# rfid_module_v3.net
KiCad netlist of a schematic drawn in EAGLE
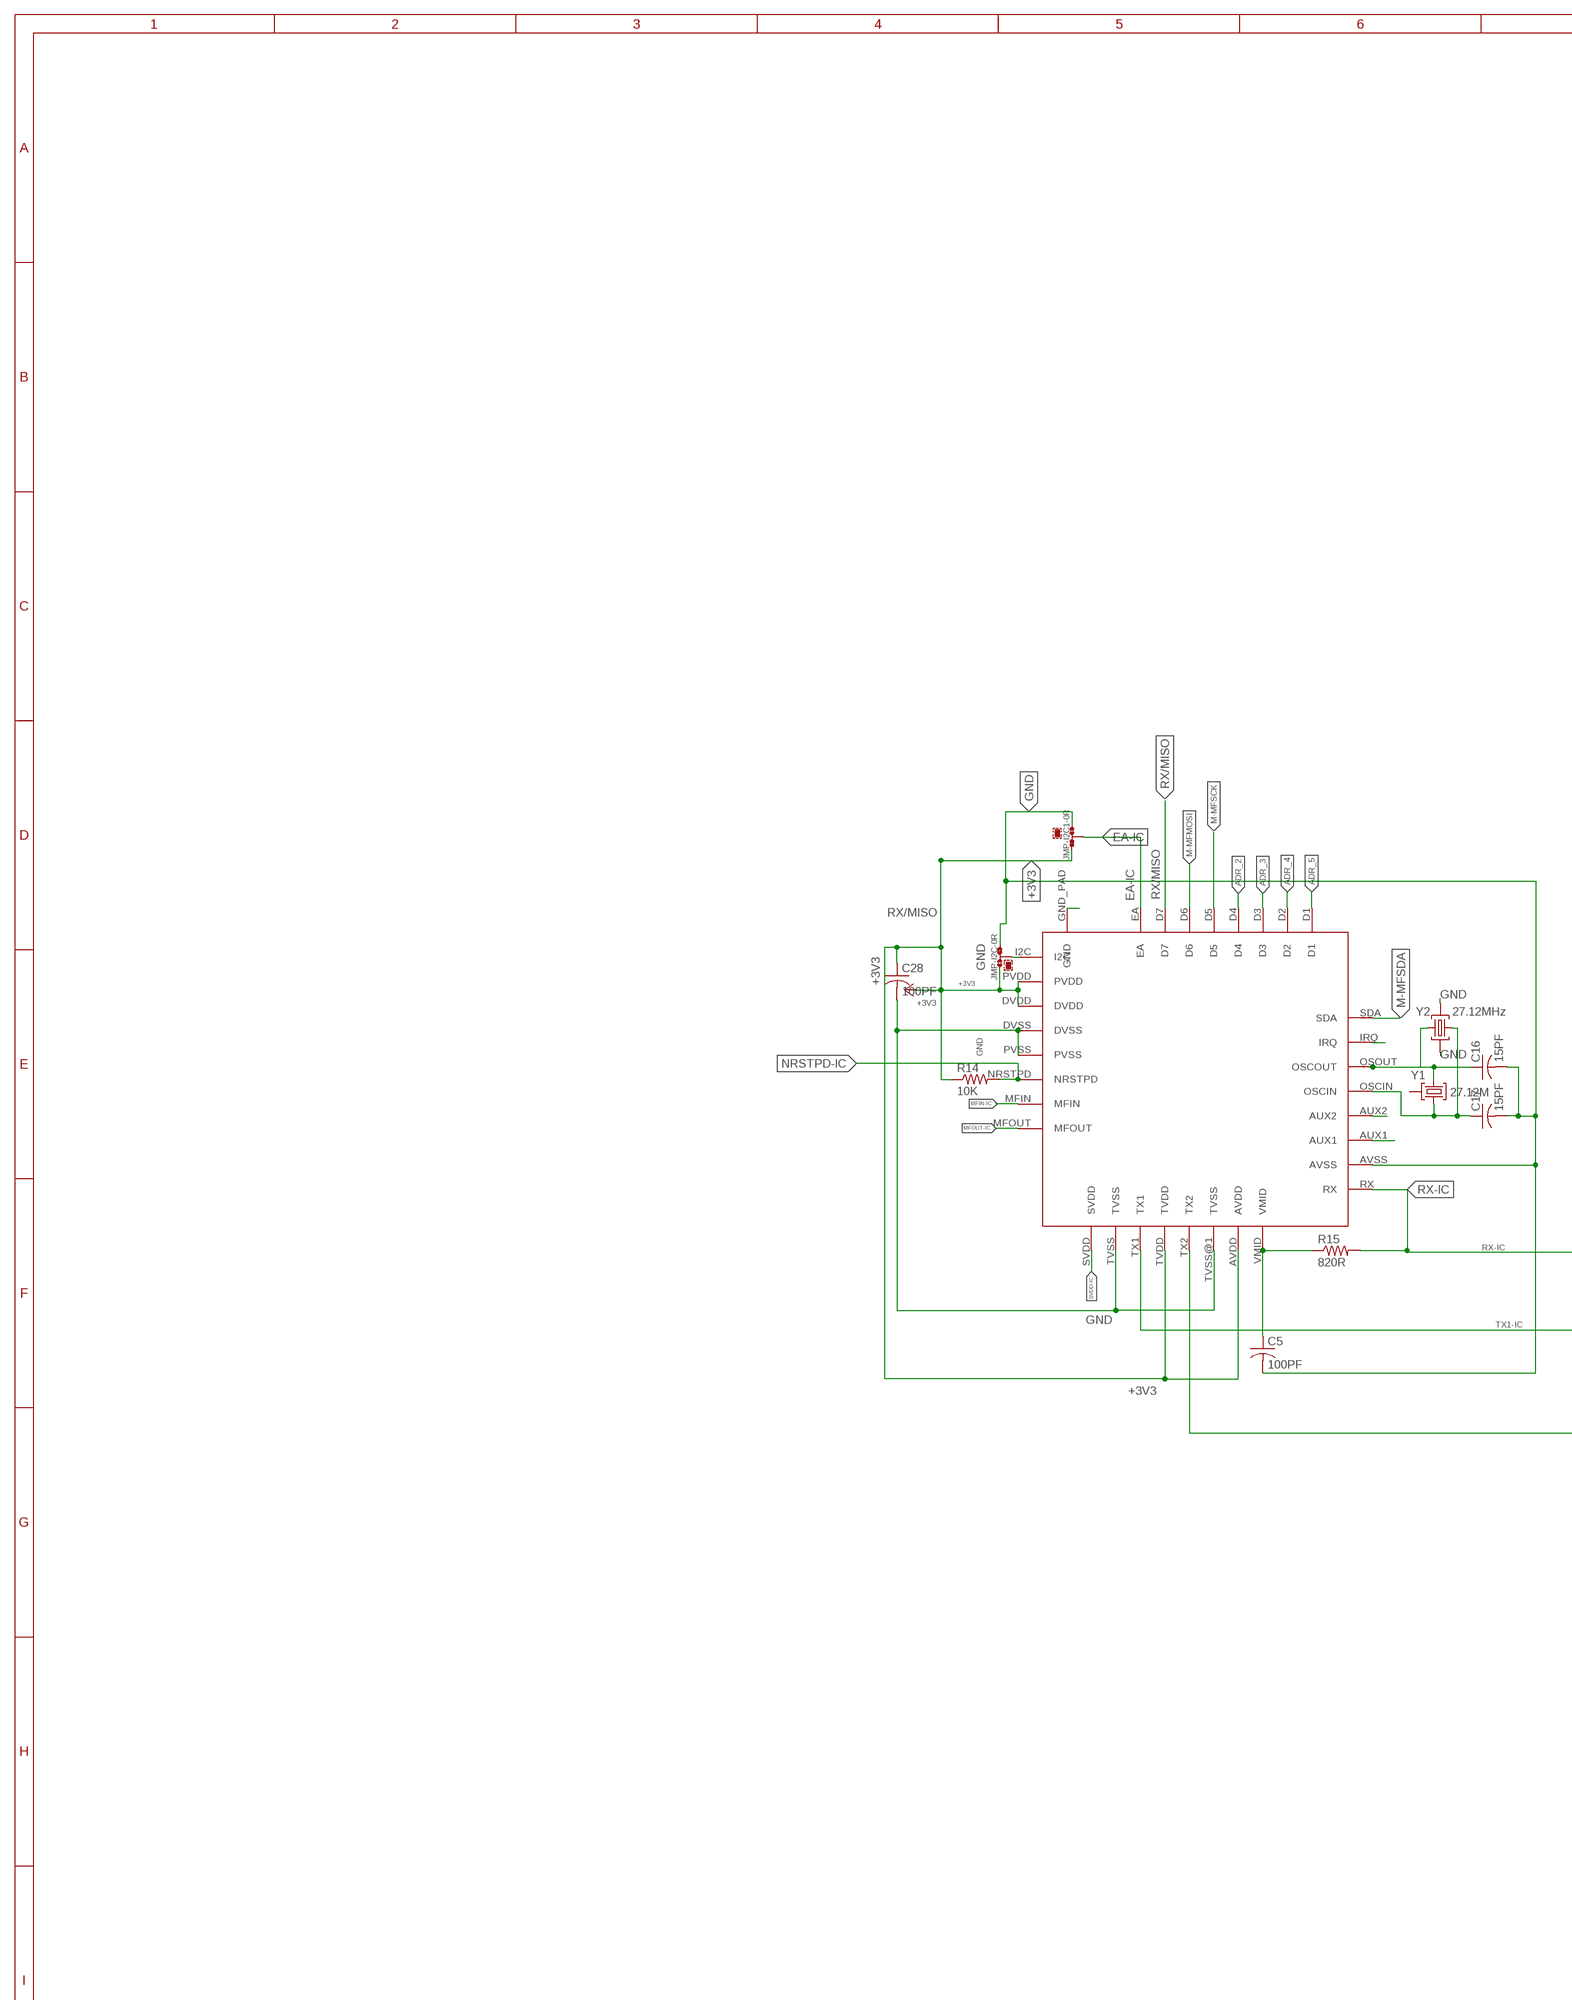
[diagram p0: schematic, sheet 1, part 1 of 2]
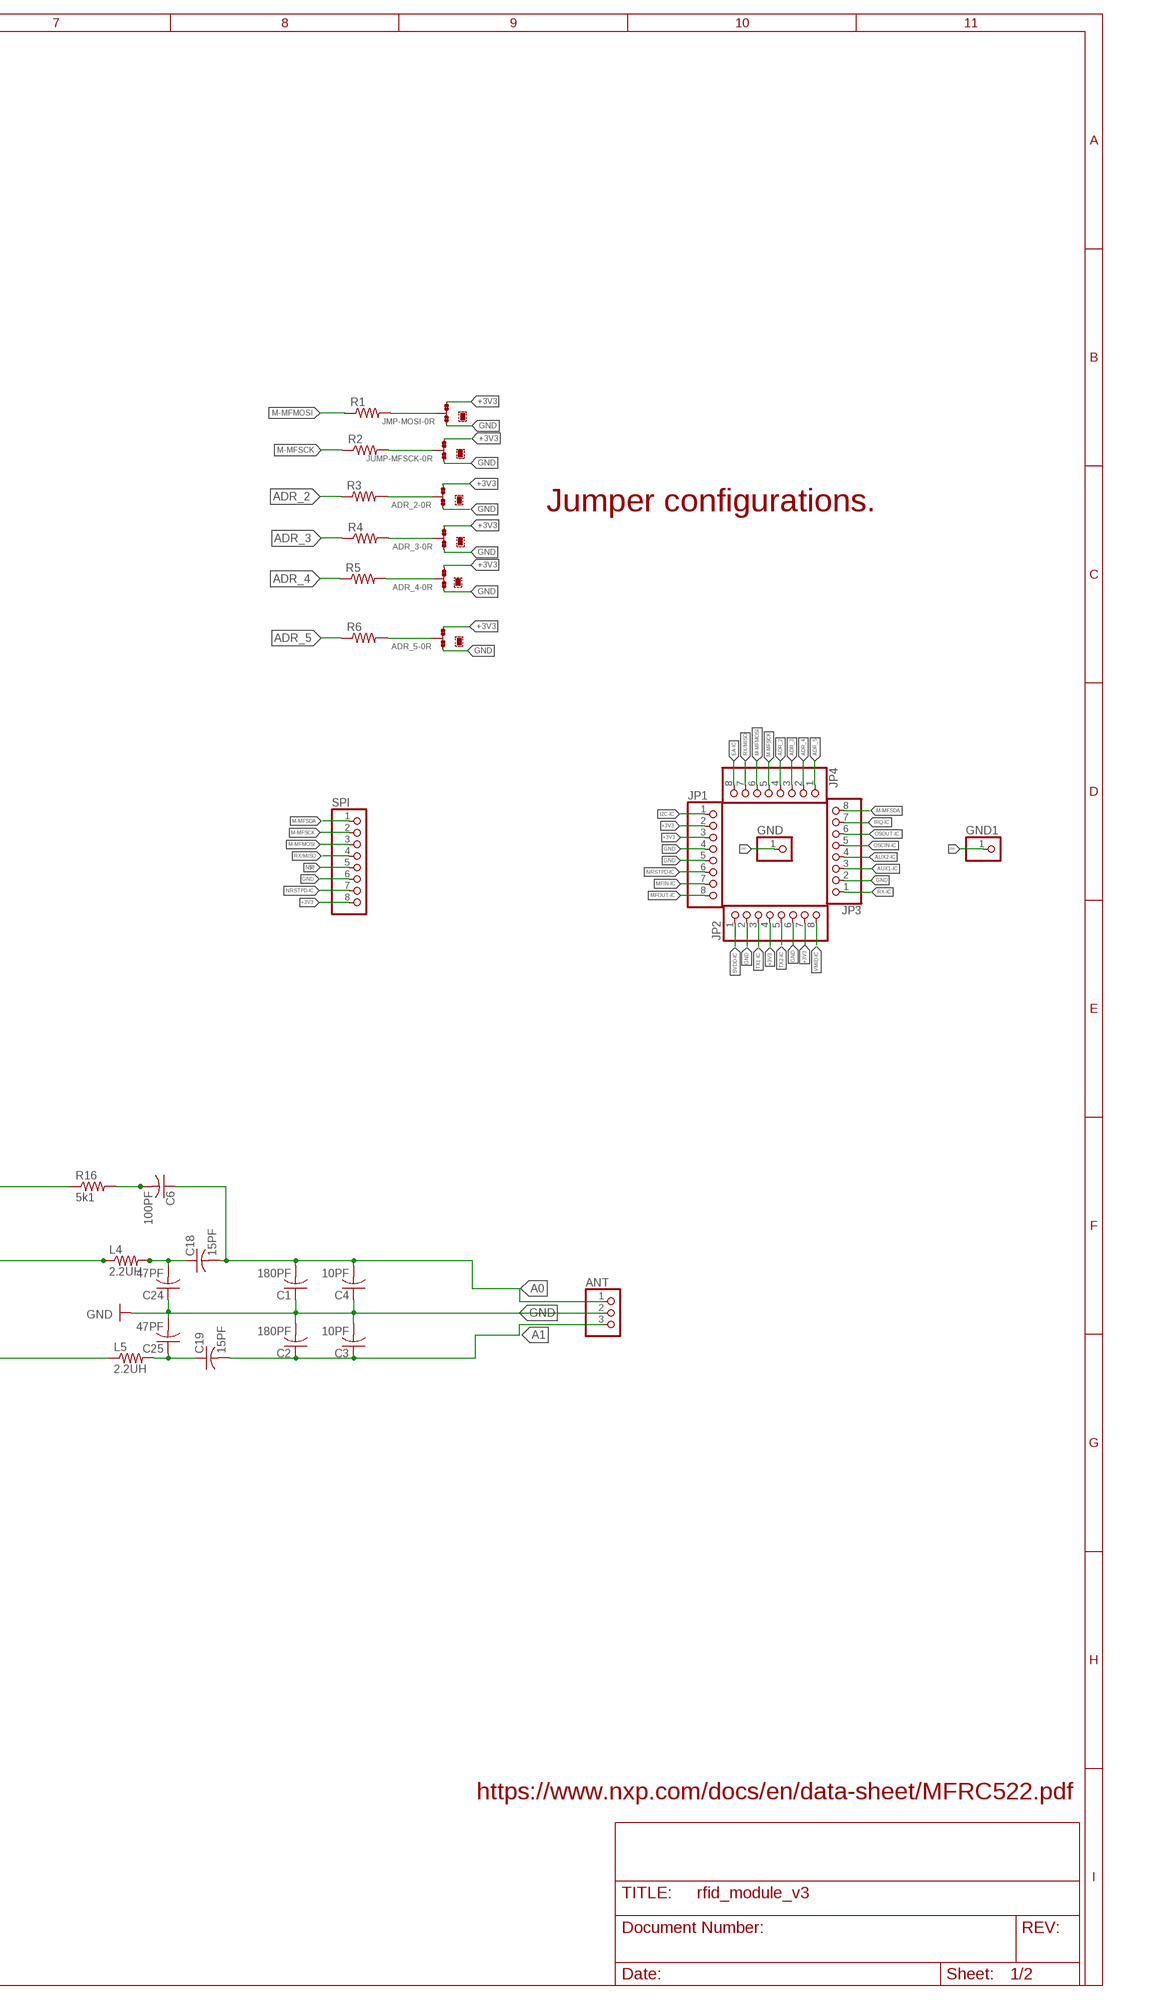
[diagram p1: schematic, sheet 1, part 2 of 2]
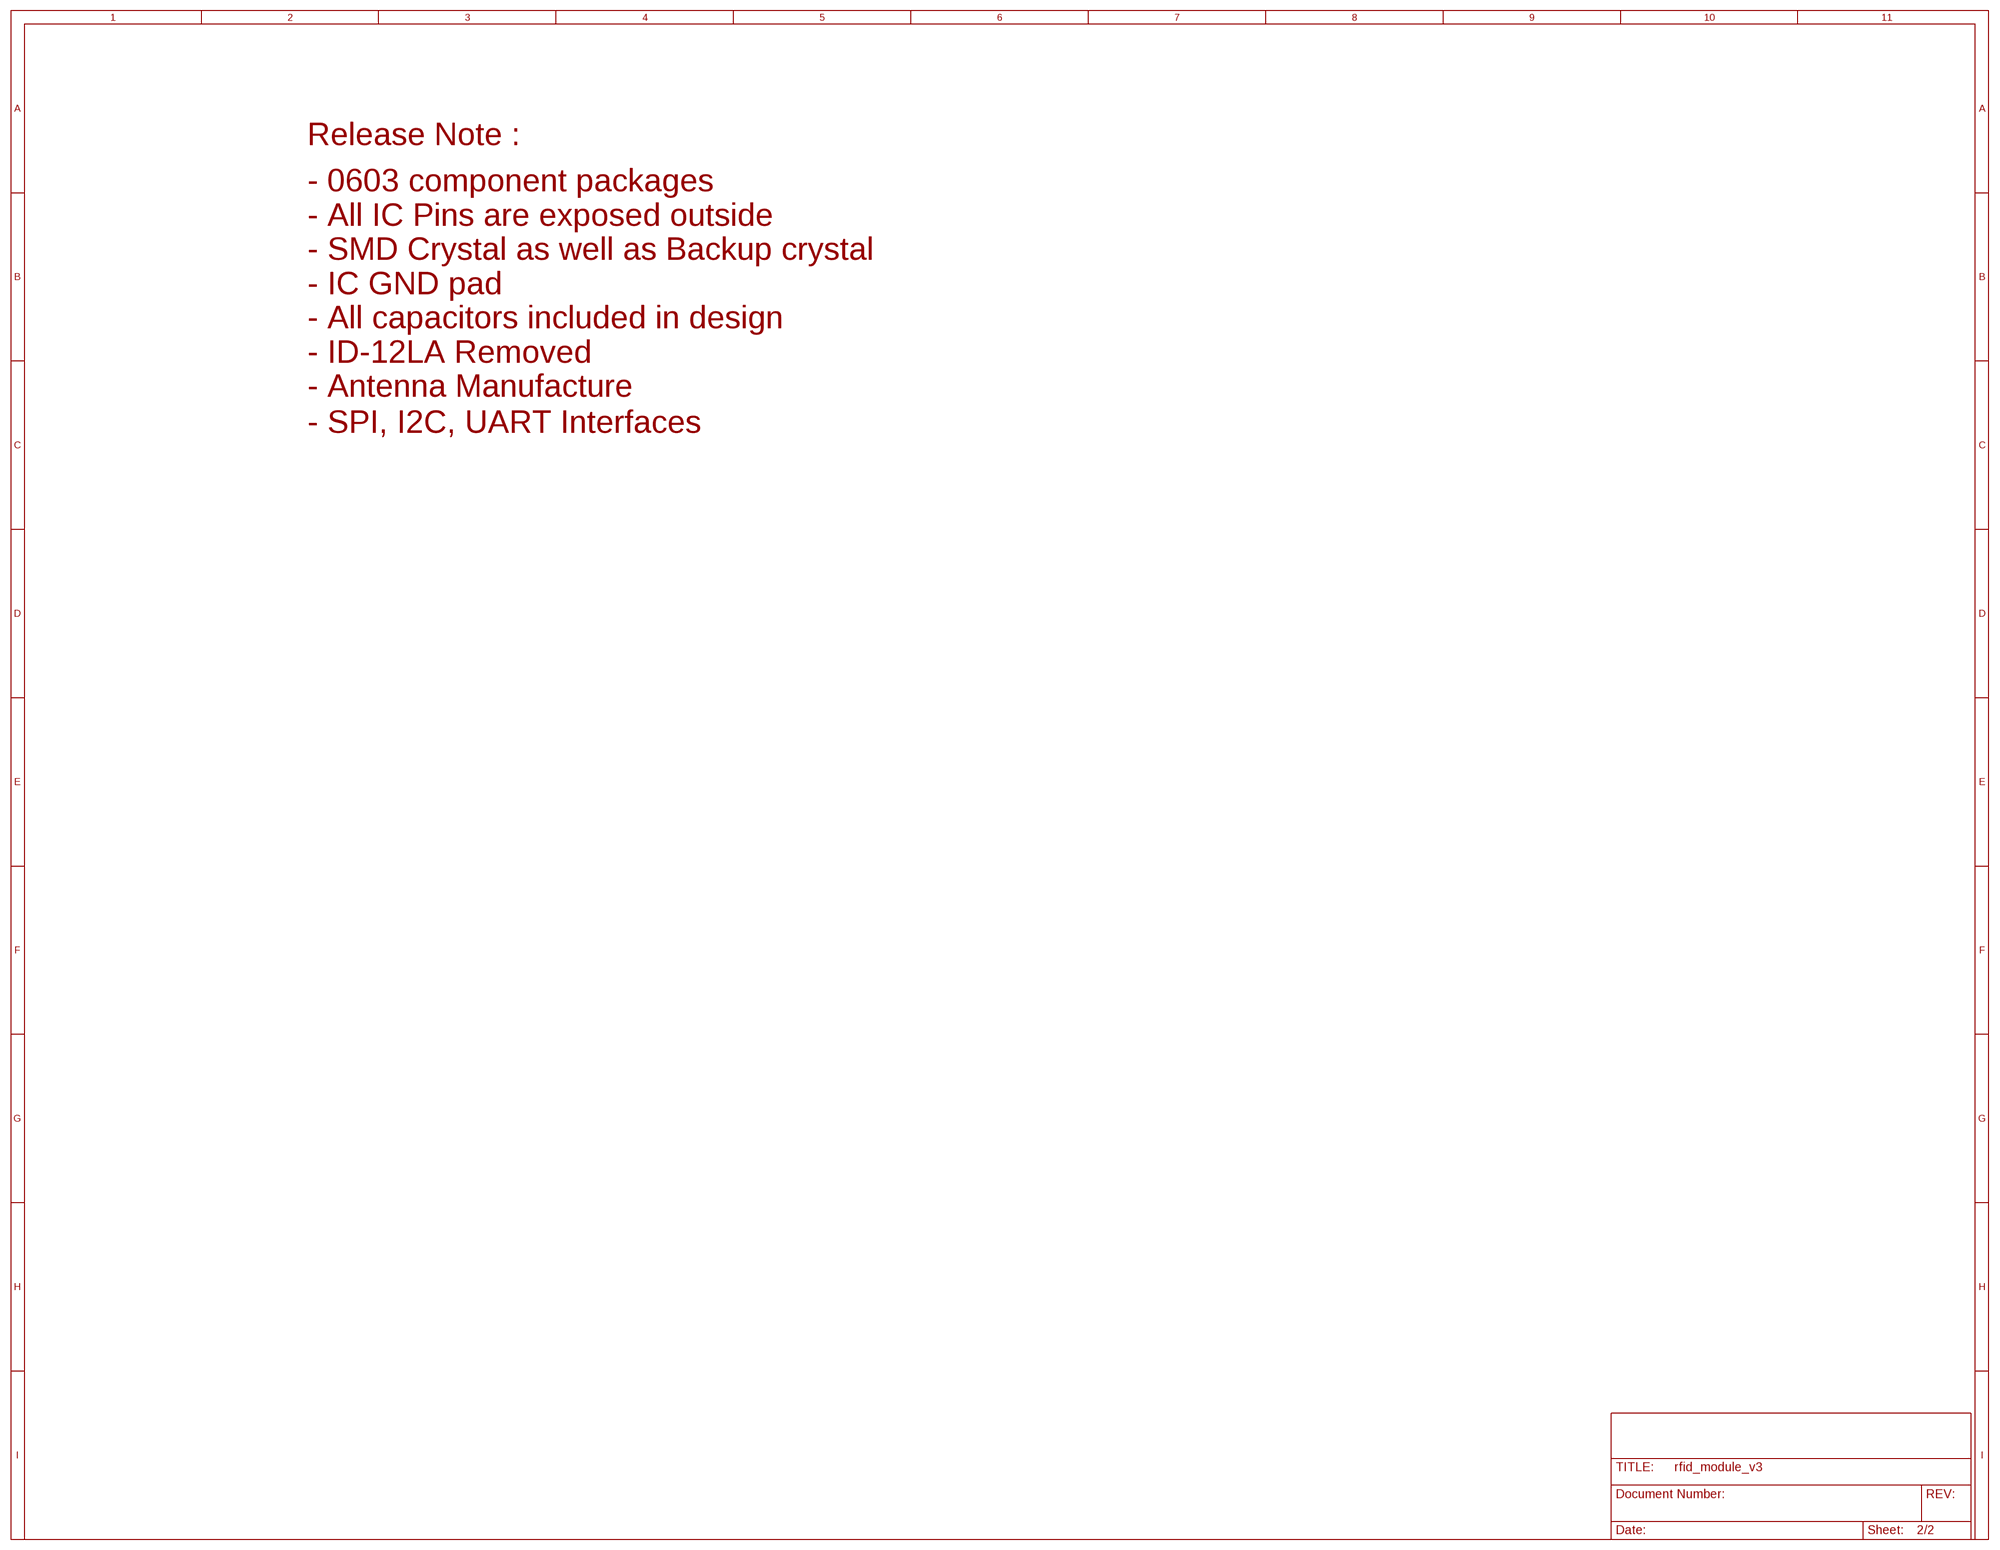
[diagram p2: schematic, sheet 2]

(export (version "E")
  (design (tool "Eeschema 10.0.6"))
  (components
    (comp (ref "ADR_2")
      (value "0R-JUMPA")
      (footprint "eagle-import:A0R-JMP")
      (libsource (lib "eagle-import") (part "0R-JUMPA"))
    )
    (comp (ref "ADR_3")
      (value "0R-JUMPA")
      (footprint "eagle-import:A0R-JMP")
      (libsource (lib "eagle-import") (part "0R-JUMPA"))
    )
    (comp (ref "ADR_4")
      (value "0R-JUMPA")
      (footprint "eagle-import:A0R-JMP")
      (libsource (lib "eagle-import") (part "0R-JUMPA"))
    )
    (comp (ref "ADR_5")
      (value "0R-JUMPA")
      (footprint "eagle-import:A0R-JMP")
      (libsource (lib "eagle-import") (part "0R-JUMPA"))
    )
    (comp (ref "ANT")
      (value "PINHD-1X3")
      (footprint "eagle-import:1X03")
      (libsource (lib "eagle-import") (part "PINHD-1X3"))
    )
    (comp (ref "C1")
      (value "180PF")
      (footprint "eagle-import:C0603")
      (libsource (lib "eagle-import") (part "C-USC0603"))
    )
    (comp (ref "C2")
      (value "180PF")
      (footprint "eagle-import:C0603")
      (libsource (lib "eagle-import") (part "C-USC0603"))
    )
    (comp (ref "C3")
      (value "10PF")
      (footprint "eagle-import:C0603")
      (libsource (lib "eagle-import") (part "C-USC0603"))
    )
    (comp (ref "C4")
      (value "10PF")
      (footprint "eagle-import:C0603")
      (libsource (lib "eagle-import") (part "C-USC0603"))
    )
    (comp (ref "C5")
      (value "100PF")
      (footprint "eagle-import:C0603")
      (libsource (lib "eagle-import") (part "C-USC0603"))
    )
    (comp (ref "C6")
      (value "100PF")
      (footprint "eagle-import:C0603")
      (libsource (lib "eagle-import") (part "C-USC0603"))
    )
    (comp (ref "C16")
      (value "15PF")
      (footprint "eagle-import:C0603")
      (libsource (lib "eagle-import") (part "C-USC0603"))
    )
    (comp (ref "C17")
      (value "15PF")
      (footprint "eagle-import:C0603")
      (libsource (lib "eagle-import") (part "C-USC0603"))
    )
    (comp (ref "C18")
      (value "15PF")
      (footprint "eagle-import:C0603")
      (libsource (lib "eagle-import") (part "C-USC0603"))
    )
    (comp (ref "C19")
      (value "15PF")
      (footprint "eagle-import:C0603")
      (libsource (lib "eagle-import") (part "C-USC0603"))
    )
    (comp (ref "C24")
      (value "47PF")
      (footprint "eagle-import:C0603")
      (libsource (lib "eagle-import") (part "C-USC0603"))
    )
    (comp (ref "C25")
      (value "47PF")
      (footprint "eagle-import:C0603")
      (libsource (lib "eagle-import") (part "C-USC0603"))
    )
    (comp (ref "C28")
      (value "100PF")
      (footprint "eagle-import:C0603")
      (libsource (lib "eagle-import") (part "C-USC0603"))
    )
    (comp (ref "GND")
      (value "PINHD-1X1")
      (footprint "eagle-import:1X01")
      (libsource (lib "eagle-import") (part "PINHD-1X1"))
    )
    (comp (ref "GND1")
      (value "PINHD-1X1")
      (footprint "eagle-import:1X01")
      (libsource (lib "eagle-import") (part "PINHD-1X1"))
    )
    (comp (ref "JMP-I2C")
      (value "0R-JUMPA")
      (footprint "eagle-import:A0R-JMP")
      (libsource (lib "eagle-import") (part "0R-JUMPA"))
    )
    (comp (ref "JMP-I2C1")
      (value "JMP-EA")
      (footprint "eagle-import:A0R-JMP")
      (libsource (lib "eagle-import") (part "0R-JUMPA"))
    )
    (comp (ref "JMP-MOSI")
      (value "0R-JUMPA")
      (footprint "eagle-import:A0R-JMP")
      (libsource (lib "eagle-import") (part "0R-JUMPA"))
    )
    (comp (ref "JP1")
      (value "PINHD-1X8")
      (footprint "eagle-import:1X08")
      (libsource (lib "eagle-import") (part "PINHD-1X8"))
    )
    (comp (ref "JP2")
      (value "PINHD-1X8")
      (footprint "eagle-import:1X08")
      (libsource (lib "eagle-import") (part "PINHD-1X8"))
    )
    (comp (ref "JP3")
      (value "PINHD-1X8")
      (footprint "eagle-import:1X08")
      (libsource (lib "eagle-import") (part "PINHD-1X8"))
    )
    (comp (ref "JP4")
      (value "PINHD-1X8")
      (footprint "eagle-import:1X08")
      (libsource (lib "eagle-import") (part "PINHD-1X8"))
    )
    (comp (ref "JUMP-MFSCK")
      (value "0R-JUMPA")
      (footprint "eagle-import:A0R-JMP")
      (libsource (lib "eagle-import") (part "0R-JUMPA"))
    )
    (comp (ref "L4")
      (value "2.2UH")
      (footprint "eagle-import:R0603")
      (libsource (lib "eagle-import") (part "R-US_R0603"))
    )
    (comp (ref "L5")
      (value "2.2UH")
      (footprint "eagle-import:R0603")
      (libsource (lib "eagle-import") (part "R-US_R0603"))
    )
    (comp (ref "R1")
      (value "R-US_R0603")
      (footprint "eagle-import:R0603")
      (libsource (lib "eagle-import") (part "R-US_R0603"))
    )
    (comp (ref "R2")
      (value "R-US_R0603")
      (footprint "eagle-import:R0603")
      (libsource (lib "eagle-import") (part "R-US_R0603"))
    )
    (comp (ref "R3")
      (value "R-US_R0603")
      (footprint "eagle-import:R0603")
      (libsource (lib "eagle-import") (part "R-US_R0603"))
    )
    (comp (ref "R4")
      (value "R-US_R0603")
      (footprint "eagle-import:R0603")
      (libsource (lib "eagle-import") (part "R-US_R0603"))
    )
    (comp (ref "R5")
      (value "R-US_R0603")
      (footprint "eagle-import:R0603")
      (libsource (lib "eagle-import") (part "R-US_R0603"))
    )
    (comp (ref "R6")
      (value "R-US_R0603")
      (footprint "eagle-import:R0603")
      (libsource (lib "eagle-import") (part "R-US_R0603"))
    )
    (comp (ref "R14")
      (value "10K")
      (footprint "eagle-import:R0603")
      (libsource (lib "eagle-import") (part "R-US_R0603"))
    )
    (comp (ref "R15")
      (value "820R")
      (footprint "eagle-import:R0603")
      (libsource (lib "eagle-import") (part "R-US_R0603"))
    )
    (comp (ref "R16")
      (value "5k1")
      (footprint "eagle-import:R0603")
      (libsource (lib "eagle-import") (part "R-US_R0603"))
    )
    (comp (ref "SPI")
      (value "PINHD-1X8")
      (footprint "eagle-import:1X08")
      (libsource (lib "eagle-import") (part "PINHD-1X8"))
    )
    (comp (ref "U$1")
      (value "MFRC522")
      (footprint "eagle-import:MFRC522")
      (libsource (lib "eagle-import") (part "MFRC522"))
    )
    (comp (ref "Y1")
      (value "27.12M")
      (footprint "eagle-import:RAD3LEAD")
      (libsource (lib "eagle-import") (part "CRYSTAL"))
    )
    (comp (ref "Y2")
      (value "27.12MHz")
      (footprint "eagle-import:CRYSTAL-3.2-2.5")
      (libsource (lib "eagle-import") (part "CRYSTAL-3.2-2.5"))
    )
  )
  (nets
    (net (code "1") (name "+3V3") (class "Default")
      (node (ref "ADR_2") (pin "3") (pinfunction "3_3") (pintype "passive"))
      (node (ref "ADR_3") (pin "3") (pinfunction "3_3") (pintype "passive"))
      (node (ref "ADR_4") (pin "3") (pinfunction "3_3") (pintype "passive"))
      (node (ref "ADR_5") (pin "3") (pinfunction "3_3") (pintype "passive"))
      (node (ref "C28") (pin "1") (pinfunction "1_1") (pintype "passive"))
      (node (ref "JMP-I2C") (pin "3") (pinfunction "3_3") (pintype "passive"))
      (node (ref "JMP-I2C1") (pin "3") (pinfunction "3_3") (pintype "passive"))
      (node (ref "JMP-MOSI") (pin "3") (pinfunction "3_3") (pintype "passive"))
      (node (ref "JP1") (pin "2") (pinfunction "2_2") (pintype "passive"))
      (node (ref "JP1") (pin "3") (pinfunction "3_3") (pintype "passive"))
      (node (ref "JP2") (pin "4") (pinfunction "4_4") (pintype "passive"))
      (node (ref "JP2") (pin "7") (pinfunction "7_7") (pintype "passive"))
      (node (ref "JUMP-MFSCK") (pin "3") (pinfunction "3_3") (pintype "passive"))
      (node (ref "R14") (pin "1") (pinfunction "1_1") (pintype "passive"))
      (node (ref "SPI") (pin "8") (pinfunction "8_8") (pintype "passive"))
      (node (ref "U$1") (pin "AVDD") (pinfunction "AVDD_AVDD") (pintype "bidirectional"))
      (node (ref "U$1") (pin "DVDD") (pinfunction "DVDD_DVDD") (pintype "bidirectional"))
      (node (ref "U$1") (pin "PVDD") (pinfunction "PVDD_PVDD") (pintype "bidirectional"))
      (node (ref "U$1") (pin "TVDD") (pinfunction "TVDD_TVDD") (pintype "bidirectional"))
    )
    (net (code "2") (name "A0") (class "Default")
      (node (ref "ANT") (pin "1") (pinfunction "1_1") (pintype "passive"))
      (node (ref "C1") (pin "2") (pinfunction "2_2") (pintype "passive"))
      (node (ref "C18") (pin "2") (pinfunction "2_2") (pintype "passive"))
      (node (ref "C4") (pin "2") (pinfunction "2_2") (pintype "passive"))
      (node (ref "C6") (pin "1") (pinfunction "1_1") (pintype "passive"))
    )
    (net (code "3") (name "A1") (class "Default")
      (node (ref "ANT") (pin "3") (pinfunction "3_3") (pintype "passive"))
      (node (ref "C19") (pin "2") (pinfunction "2_2") (pintype "passive"))
      (node (ref "C2") (pin "1") (pinfunction "1_1") (pintype "passive"))
      (node (ref "C3") (pin "1") (pinfunction "1_1") (pintype "passive"))
    )
    (net (code "4") (name "ADR_2") (class "Default")
      (node (ref "JP4") (pin "4") (pinfunction "4_4") (pintype "passive"))
      (node (ref "R3") (pin "1") (pinfunction "1_1") (pintype "passive"))
      (node (ref "U$1") (pin "D4") (pinfunction "D4_D4") (pintype "bidirectional"))
    )
    (net (code "5") (name "ADR_3") (class "Default")
      (node (ref "JP4") (pin "3") (pinfunction "3_3") (pintype "passive"))
      (node (ref "R4") (pin "1") (pinfunction "1_1") (pintype "passive"))
      (node (ref "U$1") (pin "D3") (pinfunction "D3_D3") (pintype "bidirectional"))
    )
    (net (code "6") (name "ADR_4") (class "Default")
      (node (ref "JP4") (pin "2") (pinfunction "2_2") (pintype "passive"))
      (node (ref "R5") (pin "1") (pinfunction "1_1") (pintype "passive"))
      (node (ref "U$1") (pin "D2") (pinfunction "D2_D2") (pintype "bidirectional"))
    )
    (net (code "7") (name "ADR_5") (class "Default")
      (node (ref "JP4") (pin "1") (pinfunction "1_1") (pintype "passive"))
      (node (ref "R6") (pin "1") (pinfunction "1_1") (pintype "passive"))
      (node (ref "U$1") (pin "D1") (pinfunction "D1_D1") (pintype "bidirectional"))
    )
    (net (code "8") (name "AUX1-IC") (class "Default")
      (node (ref "JP3") (pin "3") (pinfunction "3_3") (pintype "passive"))
      (node (ref "U$1") (pin "AUX1") (pinfunction "AUX1_AUX1") (pintype "bidirectional"))
    )
    (net (code "9") (name "AUX2-IC") (class "Default")
      (node (ref "JP3") (pin "4") (pinfunction "4_4") (pintype "passive"))
      (node (ref "U$1") (pin "AUX2") (pinfunction "AUX2_AUX2") (pintype "bidirectional"))
    )
    (net (code "10") (name "EA-IC") (class "Default")
      (node (ref "JMP-I2C1") (pin "2") (pinfunction "2_2") (pintype "passive"))
      (node (ref "JP4") (pin "8") (pinfunction "8_8") (pintype "passive"))
      (node (ref "U$1") (pin "EA") (pinfunction "EA_EA") (pintype "bidirectional"))
    )
    (net (code "11") (name "GND") (class "Default")
      (node (ref "ADR_2") (pin "1") (pinfunction "1_1") (pintype "passive"))
      (node (ref "ADR_3") (pin "1") (pinfunction "1_1") (pintype "passive"))
      (node (ref "ADR_4") (pin "1") (pinfunction "1_1") (pintype "passive"))
      (node (ref "ADR_5") (pin "1") (pinfunction "1_1") (pintype "passive"))
      (node (ref "ANT") (pin "2") (pinfunction "2_2") (pintype "passive"))
      (node (ref "C1") (pin "1") (pinfunction "1_1") (pintype "passive"))
      (node (ref "C16") (pin "2") (pinfunction "2_2") (pintype "passive"))
      (node (ref "C17") (pin "2") (pinfunction "2_2") (pintype "passive"))
      (node (ref "C2") (pin "2") (pinfunction "2_2") (pintype "passive"))
      (node (ref "C24") (pin "1") (pinfunction "1_1") (pintype "passive"))
      (node (ref "C25") (pin "2") (pinfunction "2_2") (pintype "passive"))
      (node (ref "C28") (pin "2") (pinfunction "2_2") (pintype "passive"))
      (node (ref "C3") (pin "2") (pinfunction "2_2") (pintype "passive"))
      (node (ref "C4") (pin "1") (pinfunction "1_1") (pintype "passive"))
      (node (ref "C5") (pin "2") (pinfunction "2_2") (pintype "passive"))
      (node (ref "GND") (pin "1") (pinfunction "1_1") (pintype "passive"))
      (node (ref "GND1") (pin "1") (pinfunction "1_1") (pintype "passive"))
      (node (ref "JMP-I2C") (pin "1") (pinfunction "1_1") (pintype "passive"))
      (node (ref "JMP-I2C1") (pin "1") (pinfunction "1_1") (pintype "passive"))
      (node (ref "JMP-MOSI") (pin "1") (pinfunction "1_1") (pintype "passive"))
      (node (ref "JP1") (pin "4") (pinfunction "4_4") (pintype "passive"))
      (node (ref "JP1") (pin "5") (pinfunction "5_5") (pintype "passive"))
      (node (ref "JP2") (pin "2") (pinfunction "2_2") (pintype "passive"))
      (node (ref "JP2") (pin "6") (pinfunction "6_6") (pintype "passive"))
      (node (ref "JP3") (pin "2") (pinfunction "2_2") (pintype "passive"))
      (node (ref "JUMP-MFSCK") (pin "1") (pinfunction "1_1") (pintype "passive"))
      (node (ref "SPI") (pin "6") (pinfunction "6_6") (pintype "passive"))
      (node (ref "U$1") (pin "AVSS") (pinfunction "AVSS_AVSS") (pintype "bidirectional"))
      (node (ref "U$1") (pin "DVSS") (pinfunction "DVSS_DVSS") (pintype "bidirectional"))
      (node (ref "U$1") (pin "GND_PAD") (pinfunction "GND_GND_PAD") (pintype "bidirectional"))
      (node (ref "U$1") (pin "PVSS") (pinfunction "PVSS_PVSS") (pintype "bidirectional"))
      (node (ref "U$1") (pin "TVSS") (pinfunction "TVSS_TVSS") (pintype "bidirectional"))
      (node (ref "U$1") (pin "TVSS@1") (pinfunction "TVSS_TVSS@1") (pintype "bidirectional"))
      (node (ref "Y2") (pin "2") (pinfunction "GND_2") (pintype "passive"))
      (node (ref "Y2") (pin "4") (pinfunction "GND_4") (pintype "passive"))
    )
    (net (code "12") (name "I2C-IC") (class "Default")
      (node (ref "JMP-I2C") (pin "2") (pinfunction "2_2") (pintype "passive"))
      (node (ref "JP1") (pin "1") (pinfunction "1_1") (pintype "passive"))
      (node (ref "U$1") (pin "I2C") (pinfunction "I2C_I2C") (pintype "bidirectional"))
    )
    (net (code "13") (name "IRQ-IC") (class "Default")
      (node (ref "JP3") (pin "7") (pinfunction "7_7") (pintype "passive"))
      (node (ref "U$1") (pin "IRQ") (pinfunction "IRQ_IRQ") (pintype "bidirectional"))
    )
    (net (code "14") (name "M-MFMOSI") (class "Default")
      (node (ref "JP4") (pin "6") (pinfunction "6_6") (pintype "passive"))
      (node (ref "R1") (pin "1") (pinfunction "1_1") (pintype "passive"))
      (node (ref "SPI") (pin "3") (pinfunction "3_3") (pintype "passive"))
      (node (ref "U$1") (pin "D6") (pinfunction "D6_D6") (pintype "bidirectional"))
    )
    (net (code "15") (name "M-MFSCK") (class "Default")
      (node (ref "JP4") (pin "5") (pinfunction "5_5") (pintype "passive"))
      (node (ref "R2") (pin "1") (pinfunction "1_1") (pintype "passive"))
      (node (ref "SPI") (pin "2") (pinfunction "2_2") (pintype "passive"))
      (node (ref "U$1") (pin "D5") (pinfunction "D5_D5") (pintype "bidirectional"))
    )
    (net (code "16") (name "M-MFSDA") (class "Default")
      (node (ref "JP3") (pin "8") (pinfunction "8_8") (pintype "passive"))
      (node (ref "SPI") (pin "1") (pinfunction "1_1") (pintype "passive"))
      (node (ref "U$1") (pin "SDA") (pinfunction "SDA_SDA") (pintype "bidirectional"))
    )
    (net (code "17") (name "MFIN-IC") (class "Default")
      (node (ref "JP1") (pin "7") (pinfunction "7_7") (pintype "passive"))
      (node (ref "U$1") (pin "MFIN") (pinfunction "MFIN_MFIN") (pintype "bidirectional"))
    )
    (net (code "18") (name "MFOUT-IC") (class "Default")
      (node (ref "JP1") (pin "8") (pinfunction "8_8") (pintype "passive"))
      (node (ref "U$1") (pin "MFOUT") (pinfunction "MFOUT_MFOUT") (pintype "bidirectional"))
    )
    (net (code "19") (name "N$8") (class "Default")
      (node (ref "SPI") (pin "5") (pinfunction "5_5") (pintype "passive"))
    )
    (net (code "20") (name "NRSTPD-IC") (class "Default")
      (node (ref "JP1") (pin "6") (pinfunction "6_6") (pintype "passive"))
      (node (ref "R14") (pin "2") (pinfunction "2_2") (pintype "passive"))
      (node (ref "SPI") (pin "7") (pinfunction "7_7") (pintype "passive"))
      (node (ref "U$1") (pin "NRSTPD") (pinfunction "NRSTPD_NRSTPD") (pintype "bidirectional"))
    )
    (net (code "21") (name "Net-(ADR_2-Pad2)") (class "Default")
      (node (ref "ADR_2") (pin "2") (pinfunction "2_2") (pintype "passive"))
      (node (ref "R3") (pin "2") (pinfunction "2_2") (pintype "passive"))
    )
    (net (code "22") (name "Net-(ADR_3-Pad2)") (class "Default")
      (node (ref "ADR_3") (pin "2") (pinfunction "2_2") (pintype "passive"))
      (node (ref "R4") (pin "2") (pinfunction "2_2") (pintype "passive"))
    )
    (net (code "23") (name "Net-(ADR_4-Pad2)") (class "Default")
      (node (ref "ADR_4") (pin "2") (pinfunction "2_2") (pintype "passive"))
      (node (ref "R5") (pin "2") (pinfunction "2_2") (pintype "passive"))
    )
    (net (code "24") (name "Net-(ADR_5-Pad2)") (class "Default")
      (node (ref "ADR_5") (pin "2") (pinfunction "2_2") (pintype "passive"))
      (node (ref "R6") (pin "2") (pinfunction "2_2") (pintype "passive"))
    )
    (net (code "25") (name "Net-(C6-Pad2)") (class "Default")
      (node (ref "C6") (pin "2") (pinfunction "2_2") (pintype "passive"))
      (node (ref "R16") (pin "2") (pinfunction "2_2") (pintype "passive"))
    )
    (net (code "26") (name "Net-(C18-Pad1)") (class "Default")
      (node (ref "C18") (pin "1") (pinfunction "1_1") (pintype "passive"))
      (node (ref "C24") (pin "2") (pinfunction "2_2") (pintype "passive"))
      (node (ref "L4") (pin "2") (pinfunction "2_2") (pintype "passive"))
    )
    (net (code "27") (name "Net-(C19-Pad1)") (class "Default")
      (node (ref "C19") (pin "1") (pinfunction "1_1") (pintype "passive"))
      (node (ref "C25") (pin "1") (pinfunction "1_1") (pintype "passive"))
      (node (ref "L5") (pin "2") (pinfunction "2_2") (pintype "passive"))
    )
    (net (code "28") (name "Net-(JMP-MOSI-Pad2)") (class "Default")
      (node (ref "JMP-MOSI") (pin "2") (pinfunction "2_2") (pintype "passive"))
      (node (ref "R1") (pin "2") (pinfunction "2_2") (pintype "passive"))
    )
    (net (code "29") (name "Net-(JUMP-MFSCK-Pad2)") (class "Default")
      (node (ref "JUMP-MFSCK") (pin "2") (pinfunction "2_2") (pintype "passive"))
      (node (ref "R2") (pin "2") (pinfunction "2_2") (pintype "passive"))
    )
    (net (code "30") (name "OSCIN-IC") (class "Default")
      (node (ref "C17") (pin "1") (pinfunction "1_1") (pintype "passive"))
      (node (ref "JP3") (pin "5") (pinfunction "5_5") (pintype "passive"))
      (node (ref "U$1") (pin "OSCIN") (pinfunction "OSCIN_OSCIN") (pintype "bidirectional"))
      (node (ref "Y1") (pin "1") (pinfunction "1_1") (pintype "passive"))
      (node (ref "Y2") (pin "1") (pinfunction "C1_1") (pintype "passive"))
    )
    (net (code "31") (name "OSOUT-IC") (class "Default")
      (node (ref "C16") (pin "1") (pinfunction "1_1") (pintype "passive"))
      (node (ref "JP3") (pin "6") (pinfunction "6_6") (pintype "passive"))
      (node (ref "U$1") (pin "OSOUT") (pinfunction "OSCOUT_OSOUT") (pintype "bidirectional"))
      (node (ref "Y1") (pin "3") (pinfunction "3_3") (pintype "passive"))
      (node (ref "Y2") (pin "3") (pinfunction "C2_3") (pintype "passive"))
    )
    (net (code "32") (name "RX-IC") (class "Default")
      (node (ref "JP3") (pin "1") (pinfunction "1_1") (pintype "passive"))
      (node (ref "R15") (pin "2") (pinfunction "2_2") (pintype "passive"))
      (node (ref "R16") (pin "1") (pinfunction "1_1") (pintype "passive"))
      (node (ref "U$1") (pin "RX") (pinfunction "RX_RX") (pintype "bidirectional"))
    )
    (net (code "33") (name "RX{slash}MISO") (class "Default")
      (node (ref "JP4") (pin "7") (pinfunction "7_7") (pintype "passive"))
      (node (ref "SPI") (pin "4") (pinfunction "4_4") (pintype "passive"))
      (node (ref "U$1") (pin "D7") (pinfunction "D7_D7") (pintype "bidirectional"))
    )
    (net (code "34") (name "SVDD-IC") (class "Default")
      (node (ref "JP2") (pin "1") (pinfunction "1_1") (pintype "passive"))
      (node (ref "U$1") (pin "SVDD") (pinfunction "SVDD_SVDD") (pintype "bidirectional"))
    )
    (net (code "35") (name "TX1-IC") (class "Default")
      (node (ref "JP2") (pin "3") (pinfunction "3_3") (pintype "passive"))
      (node (ref "L4") (pin "1") (pinfunction "1_1") (pintype "passive"))
      (node (ref "U$1") (pin "TX1") (pinfunction "TX1_TX1") (pintype "bidirectional"))
    )
    (net (code "36") (name "TX2-IC") (class "Default")
      (node (ref "JP2") (pin "5") (pinfunction "5_5") (pintype "passive"))
      (node (ref "L5") (pin "1") (pinfunction "1_1") (pintype "passive"))
      (node (ref "U$1") (pin "TX2") (pinfunction "TX2_TX2") (pintype "bidirectional"))
    )
    (net (code "37") (name "VMID-IC") (class "Default")
      (node (ref "C5") (pin "1") (pinfunction "1_1") (pintype "passive"))
      (node (ref "JP2") (pin "8") (pinfunction "8_8") (pintype "passive"))
      (node (ref "R15") (pin "1") (pinfunction "1_1") (pintype "passive"))
      (node (ref "U$1") (pin "VMID") (pinfunction "VMID_VMID") (pintype "bidirectional"))
    )
    (net (code "38") (name "unconnected-(Y1-Pad2)") (class "Default")
      (node (ref "Y1") (pin "2") (pinfunction "2_2") (pintype "passive"))
    )
  )
)
